# interface.net
KiCad netlist of a schematic drawn in Altium Designer
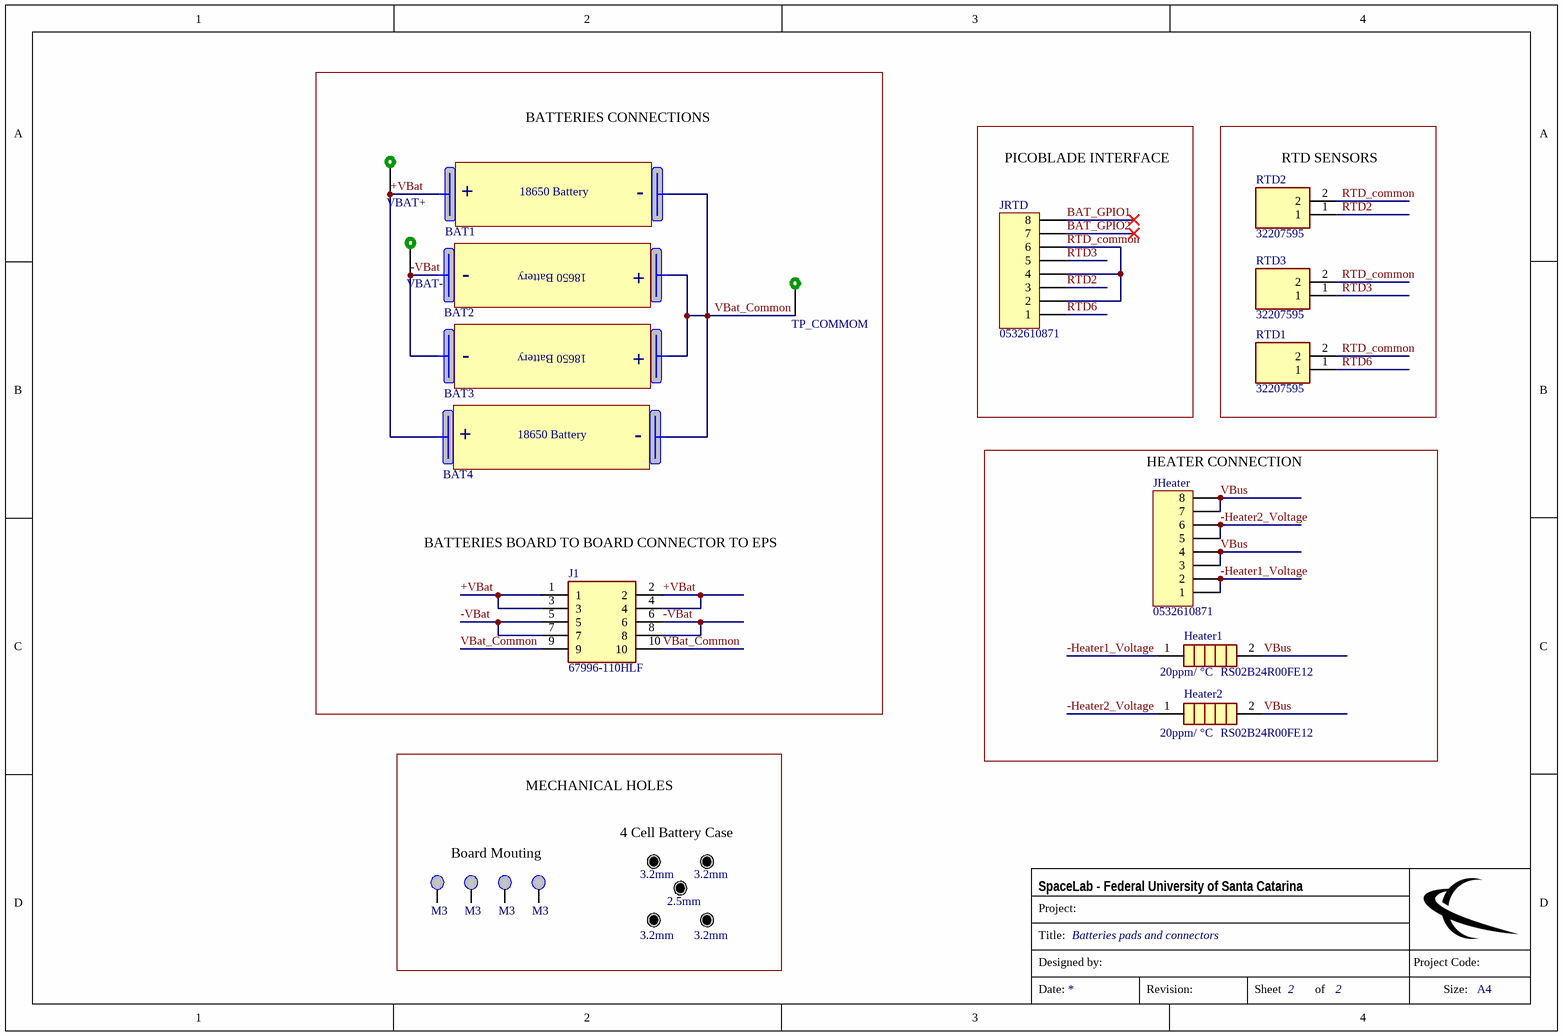
[diagram p0: interface.SchDoc]

(export (version "E")
  (design (tool "Eeschema 10.0.6"))
  (components
    (comp (ref "BAT1")
      (value "18650 Battery contact strip slot")
      (footprint "BATTERY_18650_STRIP_CONTACT")
      (description "Slot using stip contact for 18650 batterie")
      (libsource (lib "schematics_library_legacy") (part "18650_Battery_contact_strip_slot"))
    )
    (comp (ref "BAT2")
      (value "18650 Battery contact strip slot")
      (footprint "BATTERY_18650_STRIP_CONTACT")
      (description "Slot using stip contact for 18650 batterie")
      (libsource (lib "") (part "18650_Battery_contact_strip_slot_1"))
    )
    (comp (ref "BAT3")
      (value "18650 Battery contact strip slot")
      (footprint "BATTERY_18650_STRIP_CONTACT")
      (description "Slot using stip contact for 18650 batterie")
      (libsource (lib "") (part "18650_Battery_contact_strip_slot_1"))
    )
    (comp (ref "BAT4")
      (value "18650 Battery contact strip slot")
      (footprint "BATTERY_18650_STRIP_CONTACT")
      (description "Slot using stip contact for 18650 batterie")
      (libsource (lib "schematics_library_legacy") (part "18650_Battery_contact_strip_slot"))
    )
    (comp (ref "H1")
      (value "M3")
      (footprint "M3 hole")
      (description "M3 hole")
      (libsource (lib "schematics_library_legacy") (part "M3 hole"))
    )
    (comp (ref "H2")
      (value "M3")
      (footprint "M3 hole")
      (description "M3 hole")
      (libsource (lib "schematics_library_legacy") (part "M3 hole"))
    )
    (comp (ref "H3")
      (value "M3")
      (footprint "M3 hole")
      (description "M3 hole")
      (libsource (lib "schematics_library_legacy") (part "M3 hole"))
    )
    (comp (ref "H4")
      (value "M3")
      (footprint "M3 hole")
      (description "M3 hole")
      (libsource (lib "schematics_library_legacy") (part "M3 hole"))
    )
    (comp (ref "Heater1")
      (value "RS02B24R00FE12")
      (footprint "RESAD3322W86L1422D475")
      (description "Wirewound Resistors - Through Hole 3watts 24ohms 1%")
      (fields (field (name "TEMPERATURE COEFFICIENT") "20ppm/ °C"))
      (libsource (lib "schematics_library_legacy") (part "RS02B24R00FE12"))
    )
    (comp (ref "Heater2")
      (value "RS02B24R00FE12")
      (footprint "RESAD3322W86L1422D475")
      (description "Wirewound Resistors - Through Hole 3watts 24ohms 1%")
      (fields (field (name "TEMPERATURE COEFFICIENT") "20ppm/ °C"))
      (libsource (lib "schematics_library_legacy") (part "RS02B24R00FE12"))
    )
    (comp (ref "J1")
      (value "67996-110HLF")
      (footprint "HDRV10W64P254_2X5_1270X502X521P")
      (description "Headers & Wire Housings 2X5P UNSHRD HDR 30 microinch gold")
      (fields (field (name "MOUSER PART NUMBER") "649-67996-110HLF"))
      (libsource (lib "schematics_library_legacy") (part "67996-110HLF"))
    )
    (comp (ref "JHeater")
      (value "0532610871")
      (footprint "PICOBLADE 8PIN RIGHT ANGLE")
      (description "PicoBlade 8 Position Right Angle Connector Header Surface Mount 0.049\" (1.25mm)")
      (fields
        (field (name "PARTNUMBER") "53261-0871")
        (field (name "MANUFACTURER") "Molex")
        (field (name "PUBLISHER") "Altium Limited")
      )
      (libsource (lib "schematics_library_legacy") (part "0532610871"))
    )
    (comp (ref "JRTD")
      (value "0532610871")
      (footprint "PICOBLADE 8PIN RIGHT ANGLE")
      (description "PicoBlade 8 Position Right Angle Connector Header Surface Mount 0.049\" (1.25mm)")
      (fields
        (field (name "PARTNUMBER") "53261-0871")
        (field (name "MANUFACTURER") "Molex")
        (field (name "PUBLISHER") "Altium Limited")
      )
      (libsource (lib "schematics_library_legacy") (part "0532610871"))
    )
    (comp (ref "MEC1")
      (value "2.5mm battery case mount")
      (footprint "2.5mm holes battery case mount")
      (libsource (lib "schematics_library_legacy") (part "2.5mm battery case mount"))
    )
    (comp (ref "RTD1")
      (value "32207595")
      (footprint "THRMC3216X70N")
      (description "1 kOhms RTD Platinum (Pt) ±0.3% 3850ppm/°C 1206 (3216 Metric)")
      (fields (field (name "MOUSER PART NUMBER") "956-32207595"))
      (libsource (lib "schematics_library_legacy") (part "32207595"))
    )
    (comp (ref "RTD2")
      (value "32207595")
      (footprint "THRMC3216X70N")
      (description "1 kOhms RTD Platinum (Pt) ±0.3% 3850ppm/°C 1206 (3216 Metric)")
      (fields (field (name "MOUSER PART NUMBER") "956-32207595"))
      (libsource (lib "schematics_library_legacy") (part "32207595"))
    )
    (comp (ref "RTD3")
      (value "32207595")
      (footprint "THRMC3216X70N")
      (description "1 kOhms RTD Platinum (Pt) ±0.3% 3850ppm/°C 1206 (3216 Metric)")
      (fields (field (name "MOUSER PART NUMBER") "956-32207595"))
      (libsource (lib "schematics_library_legacy") (part "32207595"))
    )
    (comp (ref "TP_COMMOM")
      (value "TEST_POINT")
      (footprint "Test_Point")
      (description "Test Point")
      (libsource (lib "schematics_library_legacy") (part "TEST_POINT"))
    )
    (comp (ref "VBAT+")
      (value "TEST_POINT")
      (footprint "Test_Point")
      (description "Test Point")
      (libsource (lib "schematics_library_legacy") (part "TEST_POINT"))
    )
    (comp (ref "VBAT-")
      (value "TEST_POINT")
      (footprint "Test_Point")
      (description "Test Point")
      (libsource (lib "schematics_library_legacy") (part "TEST_POINT"))
    )
  )
  (nets
    (net (code "1") (name "/+VBat") (class "Default")
      (node (ref "BAT1") (pin "+") (pinfunction "Positive_+") (pintype "passive"))
      (node (ref "BAT4") (pin "+") (pinfunction "Positive_+") (pintype "passive"))
      (node (ref "J1") (pin "1") (pinfunction "1_1") (pintype "passive"))
      (node (ref "J1") (pin "2") (pinfunction "2_2") (pintype "passive"))
      (node (ref "J1") (pin "3") (pinfunction "3_3") (pintype "passive"))
      (node (ref "J1") (pin "4") (pinfunction "4_4") (pintype "passive"))
      (node (ref "VBAT+") (pin "1") (pinfunction "1_1") (pintype "passive"))
    )
    (net (code "2") (name "/-Heater1_Voltage") (class "Default")
      (node (ref "Heater1") (pin "1") (pinfunction "1_1") (pintype "passive"))
      (node (ref "JHeater") (pin "1") (pinfunction "1_1") (pintype "passive"))
      (node (ref "JHeater") (pin "2") (pinfunction "2_2") (pintype "passive"))
    )
    (net (code "3") (name "/-Heater2_Voltage") (class "Default")
      (node (ref "Heater2") (pin "1") (pinfunction "1_1") (pintype "passive"))
      (node (ref "JHeater") (pin "5") (pinfunction "5_5") (pintype "passive"))
      (node (ref "JHeater") (pin "6") (pinfunction "6_6") (pintype "passive"))
    )
    (net (code "4") (name "/-VBat") (class "Default")
      (node (ref "BAT2") (pin "-") (pinfunction "Negative_-") (pintype "passive"))
      (node (ref "BAT3") (pin "-") (pinfunction "Negative_-") (pintype "passive"))
      (node (ref "J1") (pin "5") (pinfunction "5_5") (pintype "passive"))
      (node (ref "J1") (pin "6") (pinfunction "6_6") (pintype "passive"))
      (node (ref "J1") (pin "7") (pinfunction "7_7") (pintype "passive"))
      (node (ref "J1") (pin "8") (pinfunction "8_8") (pintype "passive"))
      (node (ref "VBAT-") (pin "1") (pinfunction "1_1") (pintype "passive"))
    )
    (net (code "5") (name "/BAT_GPIO1") (class "Default")
      (node (ref "JRTD") (pin "8") (pinfunction "8_8") (pintype "passive+no_connect"))
    )
    (net (code "6") (name "/BAT_GPIO2") (class "Default")
      (node (ref "JRTD") (pin "7") (pinfunction "7_7") (pintype "passive+no_connect"))
    )
    (net (code "7") (name "/RTD2") (class "Default")
      (node (ref "JRTD") (pin "3") (pinfunction "3_3") (pintype "passive"))
      (node (ref "RTD2") (pin "1") (pinfunction "1_1") (pintype "passive"))
    )
    (net (code "8") (name "/RTD3") (class "Default")
      (node (ref "JRTD") (pin "5") (pinfunction "5_5") (pintype "passive"))
      (node (ref "RTD3") (pin "1") (pinfunction "1_1") (pintype "passive"))
    )
    (net (code "9") (name "/RTD6") (class "Default")
      (node (ref "JRTD") (pin "1") (pinfunction "1_1") (pintype "passive"))
      (node (ref "RTD1") (pin "1") (pinfunction "1_1") (pintype "passive"))
    )
    (net (code "10") (name "/RTD_common") (class "Default")
      (node (ref "JRTD") (pin "2") (pinfunction "2_2") (pintype "passive"))
      (node (ref "JRTD") (pin "4") (pinfunction "4_4") (pintype "passive"))
      (node (ref "JRTD") (pin "6") (pinfunction "6_6") (pintype "passive"))
      (node (ref "RTD1") (pin "2") (pinfunction "2_2") (pintype "passive"))
      (node (ref "RTD2") (pin "2") (pinfunction "2_2") (pintype "passive"))
      (node (ref "RTD3") (pin "2") (pinfunction "2_2") (pintype "passive"))
    )
    (net (code "11") (name "/VBat_Common") (class "Default")
      (node (ref "BAT1") (pin "-") (pinfunction "Negative_-") (pintype "passive"))
      (node (ref "BAT2") (pin "+") (pinfunction "Positive_+") (pintype "passive"))
      (node (ref "BAT3") (pin "+") (pinfunction "Positive_+") (pintype "passive"))
      (node (ref "BAT4") (pin "-") (pinfunction "Negative_-") (pintype "passive"))
      (node (ref "J1") (pin "10") (pinfunction "10_10") (pintype "passive"))
      (node (ref "J1") (pin "9") (pinfunction "9_9") (pintype "passive"))
      (node (ref "TP_COMMOM") (pin "1") (pinfunction "1_1") (pintype "passive"))
    )
    (net (code "12") (name "/VBus") (class "Default")
      (node (ref "Heater1") (pin "2") (pinfunction "2_2") (pintype "passive"))
      (node (ref "Heater2") (pin "2") (pinfunction "2_2") (pintype "passive"))
      (node (ref "JHeater") (pin "3") (pinfunction "3_3") (pintype "passive"))
      (node (ref "JHeater") (pin "4") (pinfunction "4_4") (pintype "passive"))
      (node (ref "JHeater") (pin "7") (pinfunction "7_7") (pintype "passive"))
      (node (ref "JHeater") (pin "8") (pinfunction "8_8") (pintype "passive"))
    )
    (net (code "13") (name "unconnected-(H1-Pad0)") (class "Default")
      (node (ref "H1") (pin "0") (pinfunction "0_0") (pintype "passive"))
    )
    (net (code "14") (name "unconnected-(H2-Pad0)") (class "Default")
      (node (ref "H2") (pin "0") (pinfunction "0_0") (pintype "passive"))
    )
    (net (code "15") (name "unconnected-(H3-Pad0)") (class "Default")
      (node (ref "H3") (pin "0") (pinfunction "0_0") (pintype "passive"))
    )
    (net (code "16") (name "unconnected-(H4-Pad0)") (class "Default")
      (node (ref "H4") (pin "0") (pinfunction "0_0") (pintype "passive"))
    )
    (net (code "17") (name "unconnected-(MEC1-Pad0)") (class "Default")
      (node (ref "MEC1") (pin "0") (pinfunction "0_0") (pintype "passive"))
    )
  )
)
